# ESP32-velky_stabilizator.net
KiCad netlist of a schematic drawn in EAGLE
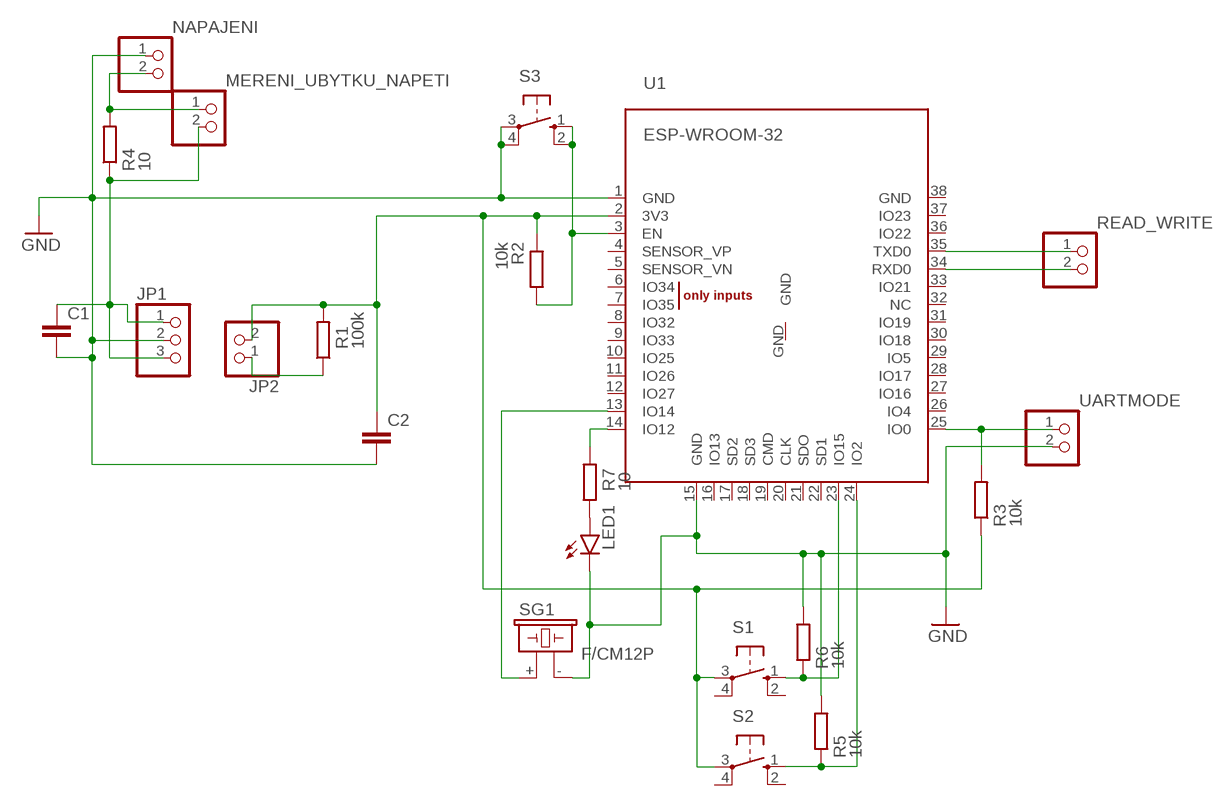
[diagram p0: schematic, sheet 1]

(export (version "E")
  (design (tool "Eeschema 10.0.6"))
  (components
    (comp (ref "C1")
      (value "C2.5/2")
      (footprint "eagle-import:C2.5-2")
      (libsource (lib "eagle-import") (part "C2.5/2"))
    )
    (comp (ref "C2")
      (value "C2.5/2")
      (footprint "eagle-import:C2.5-2")
      (libsource (lib "eagle-import") (part "C2.5/2"))
    )
    (comp (ref "JP1")
      (value "PINHD-1X3")
      (footprint "eagle-import:1X03")
      (libsource (lib "eagle-import") (part "PINHD-1X3"))
    )
    (comp (ref "JP2")
      (value "PINHD-1X2")
      (footprint "eagle-import:1X02")
      (libsource (lib "eagle-import") (part "PINHD-1X2"))
    )
    (comp (ref "LED1")
      (value "LED5MM")
      (footprint "eagle-import:LED5MM")
      (libsource (lib "eagle-import") (part "LED5MM"))
    )
    (comp (ref "MERENI_UBYTKU_NAPETI")
      (value "PINHD-1X2")
      (footprint "eagle-import:1X02")
      (libsource (lib "eagle-import") (part "PINHD-1X2"))
    )
    (comp (ref "NAPAJENI")
      (value "PINHD-1X2")
      (footprint "eagle-import:1X02")
      (libsource (lib "eagle-import") (part "PINHD-1X2"))
    )
    (comp (ref "R1")
      (value "100k")
      (footprint "eagle-import:0207_10")
      (libsource (lib "eagle-import") (part "R-EU_0207/10"))
    )
    (comp (ref "R2")
      (value "10k")
      (footprint "eagle-import:0207_10")
      (libsource (lib "eagle-import") (part "R-EU_0207/10"))
    )
    (comp (ref "R3")
      (value "10k")
      (footprint "eagle-import:0207_10")
      (libsource (lib "eagle-import") (part "R-EU_0207/10"))
    )
    (comp (ref "R4")
      (value "10")
      (footprint "eagle-import:0207_10")
      (libsource (lib "eagle-import") (part "R-EU_0207/10"))
    )
    (comp (ref "R5")
      (value "10k")
      (footprint "eagle-import:0207_10")
      (libsource (lib "eagle-import") (part "R-EU_0207/10"))
    )
    (comp (ref "R6")
      (value "10k")
      (footprint "eagle-import:0207_10")
      (libsource (lib "eagle-import") (part "R-EU_0207/10"))
    )
    (comp (ref "R7")
      (value "10")
      (footprint "eagle-import:0207_10")
      (libsource (lib "eagle-import") (part "R-EU_0207/10"))
    )
    (comp (ref "READ_WRITE")
      (value "PINHD-1X2")
      (footprint "eagle-import:1X02")
      (libsource (lib "eagle-import") (part "PINHD-1X2"))
    )
    (comp (ref "S1")
      (value "10-XX")
      (footprint "eagle-import:B3F-10XX")
      (fields (field (name "MPN") "B3F-1000"))
      (libsource (lib "eagle-import") (part "10-XX"))
    )
    (comp (ref "S2")
      (value "10-XX")
      (footprint "eagle-import:B3F-10XX")
      (fields (field (name "MPN") "B3F-1000"))
      (libsource (lib "eagle-import") (part "10-XX"))
    )
    (comp (ref "S3")
      (value "10-XX")
      (footprint "eagle-import:B3F-10XX")
      (fields (field (name "MPN") "B3F-1000"))
      (libsource (lib "eagle-import") (part "10-XX"))
    )
    (comp (ref "SG1")
      (value "F/CM12P")
      (footprint "eagle-import:F_CM12P")
      (libsource (lib "eagle-import") (part "F/CM12P"))
    )
    (comp (ref "U1")
      (value "ESP-WROOM-32")
      (footprint "eagle-import:ESP-WROOM-32")
      (libsource (lib "eagle-import") (part "ESP-WROOM-32"))
    )
    (comp (ref "UARTMODE")
      (value "PINHD-1X2")
      (footprint "eagle-import:1X02")
      (libsource (lib "eagle-import") (part "PINHD-1X2"))
    )
  )
  (nets
    (net (code "1") (name "GND") (class "Default")
      (node (ref "C1") (pin "2") (pinfunction "2_2") (pintype "passive"))
      (node (ref "C2") (pin "2") (pinfunction "2_2") (pintype "passive"))
      (node (ref "JP1") (pin "2") (pinfunction "2_2") (pintype "passive"))
      (node (ref "LED1") (pin "K") (pinfunction "C_K") (pintype "passive"))
      (node (ref "NAPAJENI") (pin "1") (pinfunction "1_1") (pintype "passive"))
      (node (ref "R5") (pin "2") (pinfunction "2_2") (pintype "passive"))
      (node (ref "R6") (pin "2") (pinfunction "2_2") (pintype "passive"))
      (node (ref "S3") (pin "3") (pinfunction "P_3") (pintype "passive"))
      (node (ref "S3") (pin "4") (pinfunction "P1_4") (pintype "passive"))
      (node (ref "SG1") (pin "-") (pinfunction "2_-") (pintype "passive"))
      (node (ref "U1") (pin "1") (pinfunction "GND_1") (pintype "bidirectional"))
      (node (ref "U1") (pin "15") (pinfunction "GND_15") (pintype "bidirectional"))
      (node (ref "UARTMODE") (pin "2") (pinfunction "2_2") (pintype "passive"))
    )
    (net (code "2") (name "Net-(C1-Pad1)") (class "Default")
      (node (ref "C1") (pin "1") (pinfunction "1_1") (pintype "passive"))
      (node (ref "JP1") (pin "1") (pinfunction "1_1") (pintype "passive"))
      (node (ref "JP1") (pin "3") (pinfunction "3_3") (pintype "passive"))
      (node (ref "MERENI_UBYTKU_NAPETI") (pin "2") (pinfunction "2_2") (pintype "passive"))
      (node (ref "R4") (pin "1") (pinfunction "1_1") (pintype "passive"))
    )
    (net (code "3") (name "Net-(JP2-Pad1)") (class "Default")
      (node (ref "JP2") (pin "1") (pinfunction "1_1") (pintype "passive"))
      (node (ref "R1") (pin "1") (pinfunction "1_1") (pintype "passive"))
    )
    (net (code "4") (name "Net-(LED1-PadA)") (class "Default")
      (node (ref "LED1") (pin "A") (pinfunction "A_A") (pintype "passive"))
      (node (ref "R7") (pin "1") (pinfunction "1_1") (pintype "passive"))
    )
    (net (code "5") (name "Net-(MERENI_UBYTKU_NAPETI-Pad1)") (class "Default")
      (node (ref "MERENI_UBYTKU_NAPETI") (pin "1") (pinfunction "1_1") (pintype "passive"))
      (node (ref "NAPAJENI") (pin "2") (pinfunction "2_2") (pintype "passive"))
      (node (ref "R4") (pin "2") (pinfunction "2_2") (pintype "passive"))
    )
    (net (code "6") (name "Net-(S1-P)") (class "Default")
      (node (ref "C2") (pin "1") (pinfunction "1_1") (pintype "passive"))
      (node (ref "JP2") (pin "2") (pinfunction "2_2") (pintype "passive"))
      (node (ref "R1") (pin "2") (pinfunction "2_2") (pintype "passive"))
      (node (ref "R2") (pin "1") (pinfunction "1_1") (pintype "passive"))
      (node (ref "R3") (pin "1") (pinfunction "1_1") (pintype "passive"))
      (node (ref "S1") (pin "3") (pinfunction "P_3") (pintype "passive"))
      (node (ref "S2") (pin "3") (pinfunction "P_3") (pintype "passive"))
      (node (ref "U1") (pin "2") (pinfunction "3V3_2") (pintype "bidirectional"))
    )
    (net (code "7") (name "Net-(S1-S)") (class "Default")
      (node (ref "R6") (pin "1") (pinfunction "1_1") (pintype "passive"))
      (node (ref "S1") (pin "1") (pinfunction "S_1") (pintype "passive"))
      (node (ref "U1") (pin "23") (pinfunction "IO15_23") (pintype "bidirectional"))
    )
    (net (code "8") (name "Net-(S2-S)") (class "Default")
      (node (ref "R5") (pin "1") (pinfunction "1_1") (pintype "passive"))
      (node (ref "S2") (pin "1") (pinfunction "S_1") (pintype "passive"))
      (node (ref "U1") (pin "24") (pinfunction "IO2_24") (pintype "bidirectional"))
    )
    (net (code "9") (name "Net-(S3-S)") (class "Default")
      (node (ref "R2") (pin "2") (pinfunction "2_2") (pintype "passive"))
      (node (ref "S3") (pin "1") (pinfunction "S_1") (pintype "passive"))
      (node (ref "S3") (pin "2") (pinfunction "S1_2") (pintype "passive"))
      (node (ref "U1") (pin "3") (pinfunction "EN_3") (pintype "bidirectional"))
    )
    (net (code "10") (name "Net-(SG1-1)") (class "Default")
      (node (ref "SG1") (pin "+") (pinfunction "1_+") (pintype "passive"))
      (node (ref "U1") (pin "13") (pinfunction "IO14_13") (pintype "bidirectional"))
    )
    (net (code "11") (name "Net-(U1-IO0)") (class "Default")
      (node (ref "R3") (pin "2") (pinfunction "2_2") (pintype "passive"))
      (node (ref "U1") (pin "25") (pinfunction "IO0_25") (pintype "bidirectional"))
      (node (ref "UARTMODE") (pin "1") (pinfunction "1_1") (pintype "passive"))
    )
    (net (code "12") (name "Net-(U1-IO12)") (class "Default")
      (node (ref "R7") (pin "2") (pinfunction "2_2") (pintype "passive"))
      (node (ref "U1") (pin "14") (pinfunction "IO12_14") (pintype "bidirectional"))
    )
    (net (code "13") (name "Net-(U1-RXD0)") (class "Default")
      (node (ref "READ_WRITE") (pin "2") (pinfunction "2_2") (pintype "passive"))
      (node (ref "U1") (pin "34") (pinfunction "RXD0_34") (pintype "bidirectional"))
    )
    (net (code "14") (name "Net-(U1-TXD0)") (class "Default")
      (node (ref "READ_WRITE") (pin "1") (pinfunction "1_1") (pintype "passive"))
      (node (ref "U1") (pin "35") (pinfunction "TXD0_35") (pintype "bidirectional"))
    )
    (net (code "15") (name "unconnected-(S1-P1-Pad4)") (class "Default")
      (node (ref "S1") (pin "4") (pinfunction "P1_4") (pintype "passive"))
    )
    (net (code "16") (name "unconnected-(S1-S1-Pad2)") (class "Default")
      (node (ref "S1") (pin "2") (pinfunction "S1_2") (pintype "passive"))
    )
    (net (code "17") (name "unconnected-(S2-P1-Pad4)") (class "Default")
      (node (ref "S2") (pin "4") (pinfunction "P1_4") (pintype "passive"))
    )
    (net (code "18") (name "unconnected-(S2-S1-Pad2)") (class "Default")
      (node (ref "S2") (pin "2") (pinfunction "S1_2") (pintype "passive"))
    )
    (net (code "19") (name "unconnected-(U1-CLK-Pad20)") (class "Default")
      (node (ref "U1") (pin "20") (pinfunction "CLK_20") (pintype "bidirectional"))
    )
    (net (code "20") (name "unconnected-(U1-CMD-Pad19)") (class "Default")
      (node (ref "U1") (pin "19") (pinfunction "CMD_19") (pintype "bidirectional"))
    )
    (net (code "21") (name "unconnected-(U1-GND-Pad38)") (class "Default")
      (node (ref "U1") (pin "38") (pinfunction "GND_38") (pintype "bidirectional"))
    )
    (net (code "22") (name "unconnected-(U1-IO4-Pad26)") (class "Default")
      (node (ref "U1") (pin "26") (pinfunction "IO4_26") (pintype "bidirectional"))
    )
    (net (code "23") (name "unconnected-(U1-IO5-Pad29)") (class "Default")
      (node (ref "U1") (pin "29") (pinfunction "IO5_29") (pintype "bidirectional"))
    )
    (net (code "24") (name "unconnected-(U1-IO13-Pad16)") (class "Default")
      (node (ref "U1") (pin "16") (pinfunction "IO13_16") (pintype "bidirectional"))
    )
    (net (code "25") (name "unconnected-(U1-IO16-Pad27)") (class "Default")
      (node (ref "U1") (pin "27") (pinfunction "IO16_27") (pintype "bidirectional"))
    )
    (net (code "26") (name "unconnected-(U1-IO17-Pad28)") (class "Default")
      (node (ref "U1") (pin "28") (pinfunction "IO17_28") (pintype "bidirectional"))
    )
    (net (code "27") (name "unconnected-(U1-IO18-Pad30)") (class "Default")
      (node (ref "U1") (pin "30") (pinfunction "IO18_30") (pintype "bidirectional"))
    )
    (net (code "28") (name "unconnected-(U1-IO19-Pad31)") (class "Default")
      (node (ref "U1") (pin "31") (pinfunction "IO19_31") (pintype "bidirectional"))
    )
    (net (code "29") (name "unconnected-(U1-IO21-Pad33)") (class "Default")
      (node (ref "U1") (pin "33") (pinfunction "IO21_33") (pintype "bidirectional"))
    )
    (net (code "30") (name "unconnected-(U1-IO22-Pad36)") (class "Default")
      (node (ref "U1") (pin "36") (pinfunction "IO22_36") (pintype "bidirectional"))
    )
    (net (code "31") (name "unconnected-(U1-IO23-Pad37)") (class "Default")
      (node (ref "U1") (pin "37") (pinfunction "IO23_37") (pintype "bidirectional"))
    )
    (net (code "32") (name "unconnected-(U1-IO25-Pad10)") (class "Default")
      (node (ref "U1") (pin "10") (pinfunction "IO25_10") (pintype "bidirectional"))
    )
    (net (code "33") (name "unconnected-(U1-IO26-Pad11)") (class "Default")
      (node (ref "U1") (pin "11") (pinfunction "IO26_11") (pintype "bidirectional"))
    )
    (net (code "34") (name "unconnected-(U1-IO27-Pad12)") (class "Default")
      (node (ref "U1") (pin "12") (pinfunction "IO27_12") (pintype "bidirectional"))
    )
    (net (code "35") (name "unconnected-(U1-IO32-Pad8)") (class "Default")
      (node (ref "U1") (pin "8") (pinfunction "IO32_8") (pintype "bidirectional"))
    )
    (net (code "36") (name "unconnected-(U1-IO33-Pad9)") (class "Default")
      (node (ref "U1") (pin "9") (pinfunction "IO33_9") (pintype "bidirectional"))
    )
    (net (code "37") (name "unconnected-(U1-IO34-Pad6)") (class "Default")
      (node (ref "U1") (pin "6") (pinfunction "IO34_6") (pintype "input"))
    )
    (net (code "38") (name "unconnected-(U1-IO35-Pad7)") (class "Default")
      (node (ref "U1") (pin "7") (pinfunction "IO35_7") (pintype "input"))
    )
    (net (code "39") (name "unconnected-(U1-NC-Pad32)") (class "Default")
      (node (ref "U1") (pin "32") (pinfunction "NC_32") (pintype "bidirectional"))
    )
    (net (code "40") (name "unconnected-(U1-PadGND)") (class "Default")
      (node (ref "U1") (pin "GND") (pinfunction "GND_GND") (pintype "bidirectional"))
    )
    (net (code "41") (name "unconnected-(U1-SD1-Pad22)") (class "Default")
      (node (ref "U1") (pin "22") (pinfunction "SD1_22") (pintype "bidirectional"))
    )
    (net (code "42") (name "unconnected-(U1-SD2-Pad17)") (class "Default")
      (node (ref "U1") (pin "17") (pinfunction "SD2_17") (pintype "bidirectional"))
    )
    (net (code "43") (name "unconnected-(U1-SD3-Pad18)") (class "Default")
      (node (ref "U1") (pin "18") (pinfunction "SD3_18") (pintype "bidirectional"))
    )
    (net (code "44") (name "unconnected-(U1-SDO-Pad21)") (class "Default")
      (node (ref "U1") (pin "21") (pinfunction "SDO_21") (pintype "bidirectional"))
    )
    (net (code "45") (name "unconnected-(U1-SENSOR_VN-Pad5)") (class "Default")
      (node (ref "U1") (pin "5") (pinfunction "SENSOR_VN_5") (pintype "input"))
    )
    (net (code "46") (name "unconnected-(U1-SENSOR_VP-Pad4)") (class "Default")
      (node (ref "U1") (pin "4") (pinfunction "SENSOR_VP_4") (pintype "input"))
    )
  )
)
